# lab2sch.net
KiCad netlist of a schematic drawn in EAGLE
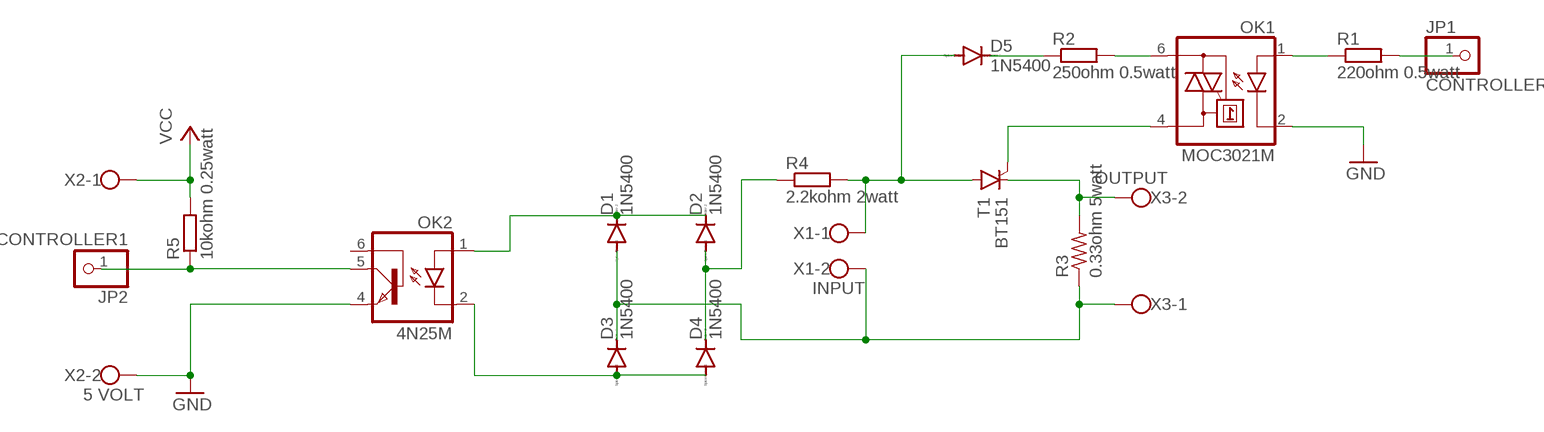
[diagram p0: schematic, sheet 1]

(export (version "E")
  (design (tool "Eeschema 10.0.6"))
  (components
    (comp (ref "D1")
      (value "1N5400")
      (footprint "eagle-import:DO201-15")
      (libsource (lib "eagle-import") (part "1N5400"))
    )
    (comp (ref "D2")
      (value "1N5400")
      (footprint "eagle-import:DO201-15")
      (libsource (lib "eagle-import") (part "1N5400"))
    )
    (comp (ref "D3")
      (value "1N5400")
      (footprint "eagle-import:DO201-15")
      (libsource (lib "eagle-import") (part "1N5400"))
    )
    (comp (ref "D4")
      (value "1N5400")
      (footprint "eagle-import:DO201-15")
      (libsource (lib "eagle-import") (part "1N5400"))
    )
    (comp (ref "D5")
      (value "1N5400")
      (footprint "eagle-import:DO201-15")
      (libsource (lib "eagle-import") (part "1N5400"))
    )
    (comp (ref "JP1")
      (value "CONTROLLER")
      (footprint "eagle-import:1X01")
      (libsource (lib "eagle-import") (part "PINHD-1X1"))
    )
    (comp (ref "JP2")
      (value "CONTROLLER1")
      (footprint "eagle-import:1X01")
      (libsource (lib "eagle-import") (part "PINHD-1X1"))
    )
    (comp (ref "OK1")
      (value "MOC3021M")
      (footprint "eagle-import:DIL06")
      (fields (field (name "MF") "FAIRCHILD SEMICONDUCTOR") (field (name "MPN") "MOC3021-M"))
      (libsource (lib "eagle-import") (part "MOC30M21"))
    )
    (comp (ref "OK2")
      (value "4N25M")
      (footprint "eagle-import:DIL06")
      (fields (field (name "MPN") "4N25-M"))
      (libsource (lib "eagle-import") (part "4N?M25"))
    )
    (comp (ref "R1")
      (value "220ohm 0.5watt")
      (footprint "eagle-import:0204_7")
      (libsource (lib "eagle-import") (part "R-EU_0204/7"))
    )
    (comp (ref "R2")
      (value "250ohm 0.5watt")
      (footprint "eagle-import:0204_7")
      (libsource (lib "eagle-import") (part "R-EU_0204/7"))
    )
    (comp (ref "R3")
      (value "0.33ohm 5watt")
      (footprint "eagle-import:0617_22")
      (libsource (lib "eagle-import") (part "R-US_0617/22"))
    )
    (comp (ref "R4")
      (value "2.2kohm 2watt")
      (footprint "eagle-import:0204_7")
      (libsource (lib "eagle-import") (part "R-EU_0204/7"))
    )
    (comp (ref "R5")
      (value "10kohm 0.25watt")
      (footprint "eagle-import:0204_7")
      (libsource (lib "eagle-import") (part "R-EU_0204/7"))
    )
    (comp (ref "T1")
      (value "BT151")
      (footprint "eagle-import:TO220CL")
      (libsource (lib "eagle-import") (part "BT151"))
    )
    (comp (ref "X1")
      (value "INPUT")
      (footprint "eagle-import:W237-102")
      (fields (field (name "MPN") "237-102"))
      (libsource (lib "eagle-import") (part "W237-102"))
    )
    (comp (ref "X2")
      (value "5 VOLT")
      (footprint "eagle-import:W237-102")
      (fields (field (name "MPN") "237-102"))
      (libsource (lib "eagle-import") (part "W237-102"))
    )
    (comp (ref "X3")
      (value "OUTPUT")
      (footprint "eagle-import:W237-102")
      (fields (field (name "MPN") "237-102"))
      (libsource (lib "eagle-import") (part "W237-102"))
    )
  )
  (nets
    (net (code "1") (name "GND") (class "Default")
      (node (ref "OK1") (pin "2") (pinfunction "C_2") (pintype "passive"))
      (node (ref "OK2") (pin "4") (pinfunction "EMI_4") (pintype "passive"))
      (node (ref "X2") (pin "2") (pinfunction "KL_2") (pintype "passive"))
    )
    (net (code "2") (name "Net-(D2-PadA)") (class "Default")
      (node (ref "D2") (pin "A") (pinfunction "A_A") (pintype "passive"))
      (node (ref "D4") (pin "C") (pinfunction "C_C") (pintype "passive"))
      (node (ref "R4") (pin "1") (pinfunction "1_1") (pintype "passive"))
    )
    (net (code "3") (name "Net-(D5-PadC)") (class "Default")
      (node (ref "D5") (pin "C") (pinfunction "C_C") (pintype "passive"))
      (node (ref "R2") (pin "1") (pinfunction "1_1") (pintype "passive"))
    )
    (net (code "4") (name "Net-(JP1-Pad1)") (class "Default")
      (node (ref "JP1") (pin "1") (pinfunction "1_1") (pintype "passive"))
      (node (ref "R1") (pin "2") (pinfunction "2_2") (pintype "passive"))
    )
    (net (code "5") (name "Net-(OK1-A)") (class "Default")
      (node (ref "OK1") (pin "1") (pinfunction "A_1") (pintype "passive"))
      (node (ref "R1") (pin "1") (pinfunction "1_1") (pintype "passive"))
    )
    (net (code "6") (name "Net-(OK1-A1)") (class "Default")
      (node (ref "OK1") (pin "4") (pinfunction "A1_4") (pintype "passive"))
      (node (ref "T1") (pin "G") (pinfunction "G_G") (pintype "passive"))
    )
    (net (code "7") (name "Net-(OK1-A2)") (class "Default")
      (node (ref "OK1") (pin "6") (pinfunction "A2_6") (pintype "passive"))
      (node (ref "R2") (pin "2") (pinfunction "2_2") (pintype "passive"))
    )
    (net (code "8") (name "Net-(OK2-A)") (class "Default")
      (node (ref "D1") (pin "C") (pinfunction "C_C") (pintype "passive"))
      (node (ref "D2") (pin "C") (pinfunction "C_C") (pintype "passive"))
      (node (ref "OK2") (pin "1") (pinfunction "A_1") (pintype "passive"))
    )
    (net (code "9") (name "Net-(OK2-C)") (class "Default")
      (node (ref "D3") (pin "A") (pinfunction "A_A") (pintype "passive"))
      (node (ref "D4") (pin "A") (pinfunction "A_A") (pintype "passive"))
      (node (ref "OK2") (pin "2") (pinfunction "C_2") (pintype "passive"))
    )
    (net (code "10") (name "Net-(OK2-COL)") (class "Default")
      (node (ref "JP2") (pin "1") (pinfunction "1_1") (pintype "passive"))
      (node (ref "OK2") (pin "5") (pinfunction "COL_5") (pintype "passive"))
      (node (ref "R5") (pin "1") (pinfunction "1_1") (pintype "passive"))
    )
    (net (code "11") (name "Net-(X1A-KL)") (class "Default")
      (node (ref "D5") (pin "A") (pinfunction "A_A") (pintype "passive"))
      (node (ref "R4") (pin "2") (pinfunction "2_2") (pintype "passive"))
      (node (ref "T1") (pin "A") (pinfunction "A_A") (pintype "passive"))
      (node (ref "X1") (pin "1") (pinfunction "KL_1") (pintype "passive"))
    )
    (net (code "12") (name "Net-(X1B-KL)") (class "Default")
      (node (ref "D1") (pin "A") (pinfunction "A_A") (pintype "passive"))
      (node (ref "D3") (pin "C") (pinfunction "C_C") (pintype "passive"))
      (node (ref "R3") (pin "1") (pinfunction "1_1") (pintype "passive"))
      (node (ref "X1") (pin "2") (pinfunction "KL_2") (pintype "passive"))
      (node (ref "X3") (pin "1") (pinfunction "KL_1") (pintype "passive"))
    )
    (net (code "13") (name "Net-(X3B-KL)") (class "Default")
      (node (ref "R3") (pin "2") (pinfunction "2_2") (pintype "passive"))
      (node (ref "T1") (pin "C") (pinfunction "C_C") (pintype "passive"))
      (node (ref "X3") (pin "2") (pinfunction "KL_2") (pintype "passive"))
    )
    (net (code "14") (name "VCC") (class "Default")
      (node (ref "R5") (pin "2") (pinfunction "2_2") (pintype "passive"))
      (node (ref "X2") (pin "1") (pinfunction "KL_1") (pintype "passive"))
    )
    (net (code "15") (name "unconnected-(OK2-BAS-Pad6)") (class "Default")
      (node (ref "OK2") (pin "6") (pinfunction "BAS_6") (pintype "passive"))
    )
  )
)
